# B_I_m___u.net
KiCad netlist of a schematic drawn in Altium Designer
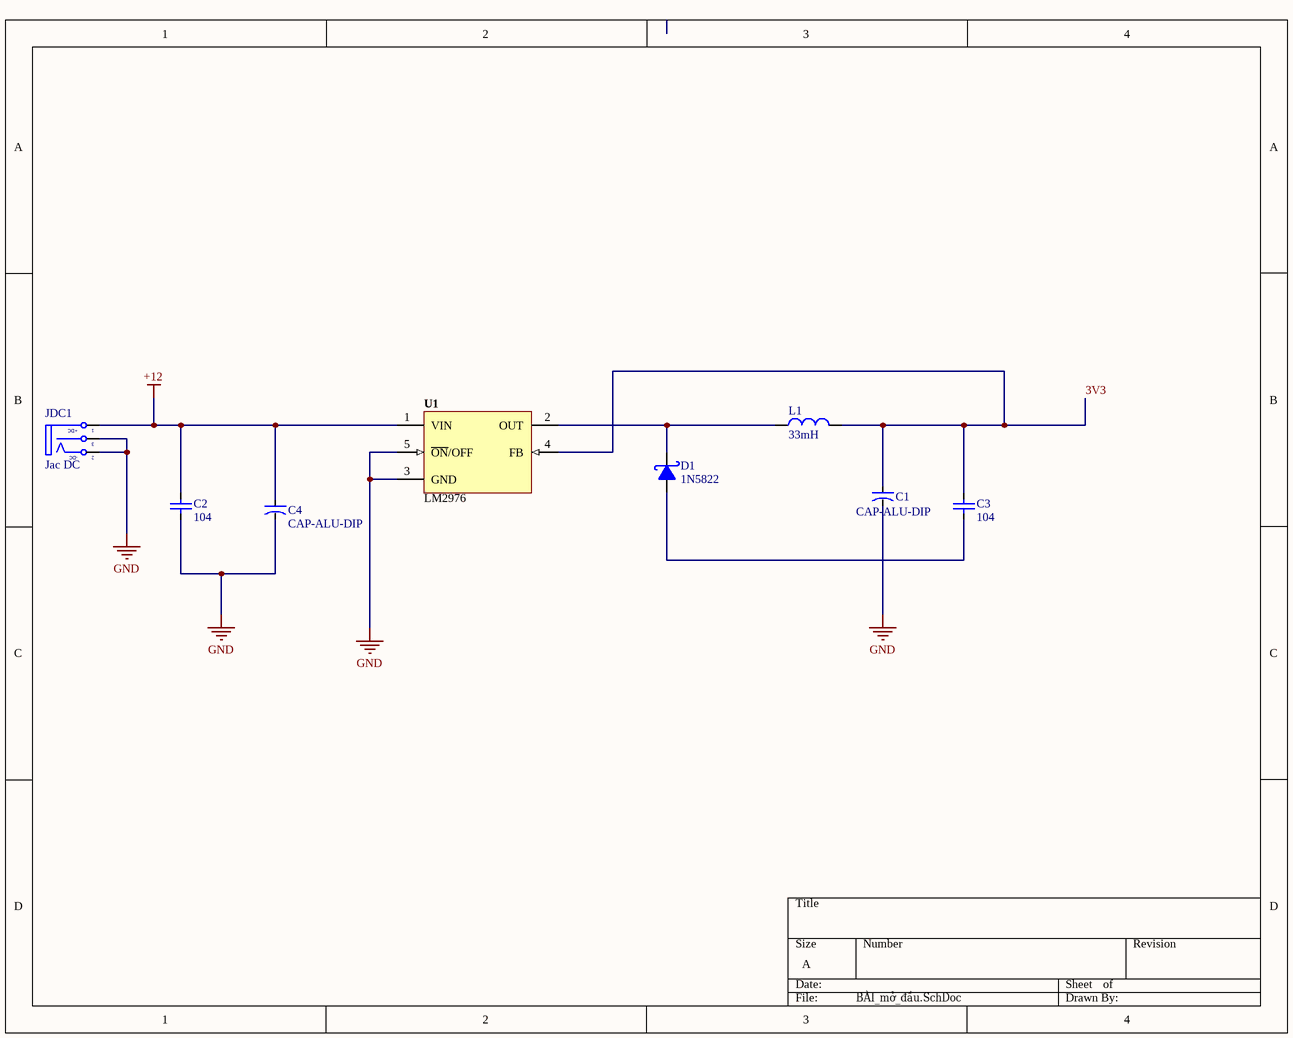
[diagram p0: BÀI_mở_đầu.SchDoc]

(export (version "E")
  (design (tool "Eeschema 10.0.6"))
  (components
    (comp (ref "C1")
      (value "CAP-ALU-DIP")
      (footprint "CA-ALU-2.54")
      (description "Capacitor (Semiconductor SIM Model)")
      (fields (field (name "PUBLISHER") "Altium Limited"))
      (libsource (lib "My-Library") (part "CAP-ALU-DIP"))
    )
    (comp (ref "C2")
      (value "104")
      (footprint "CAP_0805")
      (description "Capacitor")
      (fields (field (name "PUBLISHER") "Altium Limited"))
      (libsource (lib "My-Library") (part "CapSMD"))
    )
    (comp (ref "C3")
      (value "104")
      (footprint "CAP_0805")
      (description "Capacitor")
      (fields (field (name "PUBLISHER") "Altium Limited"))
      (libsource (lib "My-Library") (part "CapSMD"))
    )
    (comp (ref "C4")
      (value "CAP-ALU-DIP")
      (footprint "CA-ALU-2.54")
      (description "Capacitor (Semiconductor SIM Model)")
      (fields (field (name "PUBLISHER") "Altium Limited"))
      (libsource (lib "My-Library") (part "CAP-ALU-DIP"))
    )
    (comp (ref "D1")
      (value "1N5822")
      (footprint "SMA")
      (description "Schottky Rectifiers")
      (libsource (lib "My-Library") (part "1N5822"))
    )
    (comp (ref "JDC1")
      (value "Jac DC")
      (footprint "DC-IN")
      (description "Jac DC input")
      (libsource (lib "My-Library") (part "DCIN"))
    )
    (comp (ref "L1")
      (value "33mH")
      (footprint "L-SMD-M-12x10")
      (description "Inductor")
      (libsource (lib "My-Library") (part "Inductor"))
    )
    (comp (ref "U1") (value "LM2976") (footprint "TO263-5") (libsource (lib "My-Library") (part "LM2596")))
  )
  (nets
    (net (code "1") (name "+12") (class "Default")
      (node (ref "C2") (pin "2") (pinfunction "2_2") (pintype "passive"))
      (node (ref "C4") (pin "1") (pinfunction "1_1") (pintype "passive"))
      (node (ref "JDC1") (pin "1") (pinfunction "T_1") (pintype "passive"))
      (node (ref "U1") (pin "1") (pinfunction "VIN_1") (pintype "power_in"))
    )
    (net (code "2") (name "/3V3") (class "Default")
      (node (ref "C1") (pin "1") (pinfunction "1_1") (pintype "passive"))
      (node (ref "C3") (pin "2") (pinfunction "2_2") (pintype "passive"))
      (node (ref "L1") (pin "2") (pinfunction "2_2") (pintype "passive"))
      (node (ref "U1") (pin "4") (pinfunction "FB_4") (pintype "input"))
    )
    (net (code "3") (name "GND") (class "Default")
      (node (ref "C1") (pin "2") (pinfunction "2_2") (pintype "passive"))
      (node (ref "C2") (pin "1") (pinfunction "1_1") (pintype "passive"))
      (node (ref "C4") (pin "2") (pinfunction "2_2") (pintype "passive"))
      (node (ref "JDC1") (pin "2") (pinfunction "TN_2") (pintype "passive"))
      (node (ref "JDC1") (pin "3") (pinfunction "S_3") (pintype "power_in"))
      (node (ref "U1") (pin "3") (pinfunction "GND_3") (pintype "power_in"))
      (node (ref "U1") (pin "5") (pinfunction "~{ON}/OFF_5") (pintype "input"))
    )
    (net (code "4") (name "Net-(D1-A)") (class "Default")
      (node (ref "C3") (pin "1") (pinfunction "1_1") (pintype "passive"))
      (node (ref "D1") (pin "1") (pinfunction "A_1") (pintype "passive"))
    )
    (net (code "5") (name "Net-(D1-K)") (class "Default")
      (node (ref "D1") (pin "2") (pinfunction "K_2") (pintype "passive"))
      (node (ref "L1") (pin "1") (pinfunction "1_1") (pintype "passive"))
      (node (ref "U1") (pin "2") (pinfunction "OUT_2") (pintype "power_in"))
    )
  )
)
